# FSE_TSAL_trigger_schematic.net
KiCad netlist of a schematic drawn in EAGLE
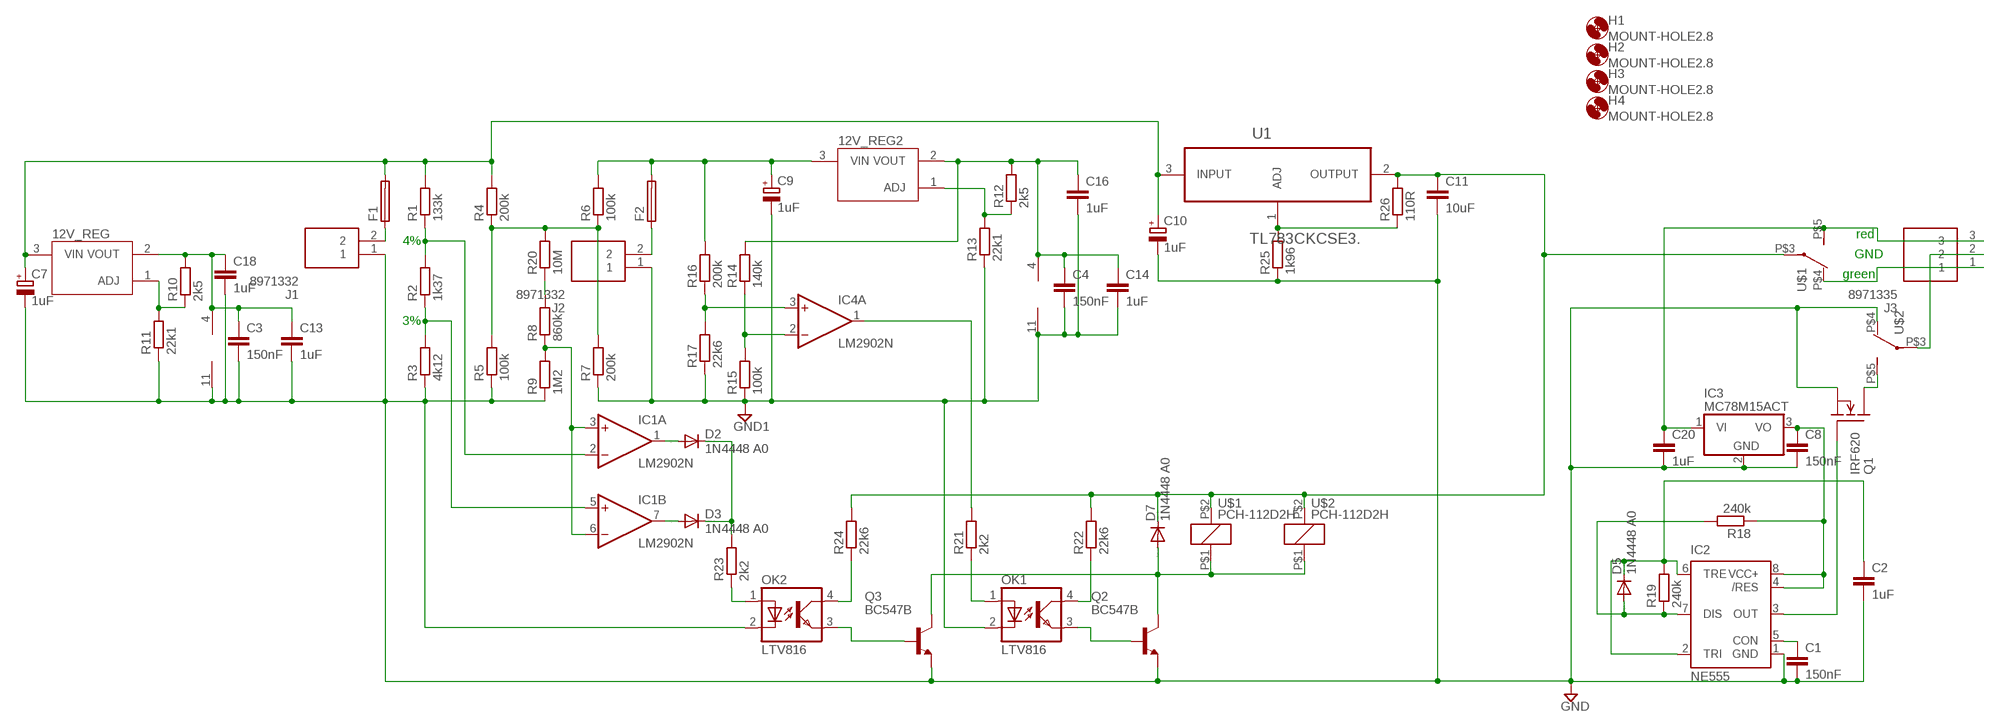
[diagram p0: schematic, sheet 1]

(export (version "E")
  (design (tool "Eeschema 10.0.6"))
  (components
    (comp (ref "12V_REG")
      (value "LR8LR8")
      (footprint "eagle-import:TO92-LINE")
      (libsource (lib "eagle-import") (part "LR8LR8"))
    )
    (comp (ref "12V_REG2")
      (value "LR8LR8")
      (footprint "eagle-import:TO92-LINE")
      (libsource (lib "eagle-import") (part "LR8LR8"))
    )
    (comp (ref "C1")
      (value "150nF")
      (footprint "eagle-import:C050-024X044")
      (libsource (lib "eagle-import") (part "C-EU050-024X044"))
    )
    (comp (ref "C2")
      (value "1uF")
      (footprint "eagle-import:C025-030X050")
      (libsource (lib "eagle-import") (part "C-EU025-030X050"))
    )
    (comp (ref "C3")
      (value "150nF")
      (footprint "eagle-import:C050-024X044")
      (libsource (lib "eagle-import") (part "C-EU050-024X044"))
    )
    (comp (ref "C4")
      (value "150nF")
      (footprint "eagle-import:C050-024X044")
      (libsource (lib "eagle-import") (part "C-EU050-024X044"))
    )
    (comp (ref "C7")
      (value "1uF")
      (footprint "eagle-import:E3,5-8")
      (libsource (lib "eagle-import") (part "CPOL-EUE3.5-8"))
    )
    (comp (ref "C8")
      (value "150nF")
      (footprint "eagle-import:C050-024X044")
      (libsource (lib "eagle-import") (part "C-EU050-024X044"))
    )
    (comp (ref "C9")
      (value "1uF")
      (footprint "eagle-import:E3,5-8")
      (libsource (lib "eagle-import") (part "CPOL-EUE3.5-8"))
    )
    (comp (ref "C10")
      (value "1uF")
      (footprint "eagle-import:E3,5-8")
      (libsource (lib "eagle-import") (part "CPOL-EUE3.5-8"))
    )
    (comp (ref "C11")
      (value "10uF")
      (footprint "eagle-import:C050-075X075")
      (libsource (lib "eagle-import") (part "C-EU050-075X075"))
    )
    (comp (ref "C13")
      (value "1uF")
      (footprint "eagle-import:C025-030X050")
      (libsource (lib "eagle-import") (part "C-EU025-030X050"))
    )
    (comp (ref "C14")
      (value "1uF")
      (footprint "eagle-import:C025-030X050")
      (libsource (lib "eagle-import") (part "C-EU025-030X050"))
    )
    (comp (ref "C16")
      (value "1uF")
      (footprint "eagle-import:C025-030X050")
      (libsource (lib "eagle-import") (part "C-EU025-030X050"))
    )
    (comp (ref "C18")
      (value "1uF")
      (footprint "eagle-import:C025-030X050")
      (libsource (lib "eagle-import") (part "C-EU025-030X050"))
    )
    (comp (ref "C20")
      (value "1uF")
      (footprint "eagle-import:C025-030X050")
      (libsource (lib "eagle-import") (part "C-EU025-030X050"))
    )
    (comp (ref "D2")
      (value "1N4448 A0")
      (footprint "eagle-import:DO35-10")
      (libsource (lib "eagle-import") (part "1N4446"))
    )
    (comp (ref "D3")
      (value "1N4448 A0")
      (footprint "eagle-import:DO35-10")
      (libsource (lib "eagle-import") (part "1N4446"))
    )
    (comp (ref "D5")
      (value "1N4448 A0")
      (footprint "eagle-import:DO35-10")
      (libsource (lib "eagle-import") (part "1N4446"))
    )
    (comp (ref "D7")
      (value "1N4448 A0")
      (footprint "eagle-import:DO35-10")
      (libsource (lib "eagle-import") (part "1N4446"))
    )
    (comp (ref "F1")
      (value "GSH15")
      (footprint "eagle-import:GSH15")
      (fields (field (name "MPN") "64900001039"))
      (libsource (lib "eagle-import") (part "GSH15"))
    )
    (comp (ref "F2")
      (value "GSH15")
      (footprint "eagle-import:GSH15")
      (fields (field (name "MPN") "64900001039"))
      (libsource (lib "eagle-import") (part "GSH15"))
    )
    (comp (ref "H1")
      (value "MOUNT-HOLE2.8")
      (footprint "eagle-import:2,8")
      (libsource (lib "eagle-import") (part "MOUNT-HOLE2.8"))
    )
    (comp (ref "H2")
      (value "MOUNT-HOLE2.8")
      (footprint "eagle-import:2,8")
      (libsource (lib "eagle-import") (part "MOUNT-HOLE2.8"))
    )
    (comp (ref "H3")
      (value "MOUNT-HOLE2.8")
      (footprint "eagle-import:2,8")
      (libsource (lib "eagle-import") (part "MOUNT-HOLE2.8"))
    )
    (comp (ref "H4")
      (value "MOUNT-HOLE2.8")
      (footprint "eagle-import:2,8")
      (libsource (lib "eagle-import") (part "MOUNT-HOLE2.8"))
    )
    (comp (ref "IC1")
      (value "LM2902N")
      (footprint "eagle-import:DIL14")
      (libsource (lib "eagle-import") (part "LM2902N"))
    )
    (comp (ref "IC2")
      (value "NE555")
      (footprint "eagle-import:DIL-08")
      (fields (field (name "MF") "Arrow Electronics") (field (name "MPN") "NE555N"))
      (libsource (lib "eagle-import") (part "NE555"))
    )
    (comp (ref "IC3")
      (value "MC78M15ACT")
      (footprint "eagle-import:TO220V")
      (libsource (lib "eagle-import") (part "MC78MT15AC"))
    )
    (comp (ref "IC4")
      (value "LM2902N")
      (footprint "eagle-import:DIL14")
      (libsource (lib "eagle-import") (part "LM2902N"))
    )
    (comp (ref "J1")
      (value "8971332")
      (footprint "eagle-import:SHDR2W90P0X350_1X2_700X700X850")
      (libsource (lib "eagle-import") (part "8971332"))
    )
    (comp (ref "J2")
      (value "8971332")
      (footprint "eagle-import:SHDR2W90P0X350_1X2_700X700X850")
      (libsource (lib "eagle-import") (part "8971332"))
    )
    (comp (ref "J3")
      (value "8971335")
      (footprint "eagle-import:SHDR3W90P0X350_1X3_1050X700X85")
      (libsource (lib "eagle-import") (part "8971335"))
    )
    (comp (ref "OK1")
      (value "LTV816")
      (footprint "eagle-import:DIL04")
      (libsource (lib "eagle-import") (part "LTV816"))
    )
    (comp (ref "OK2")
      (value "LTV816")
      (footprint "eagle-import:DIL04")
      (libsource (lib "eagle-import") (part "LTV816"))
    )
    (comp (ref "Q1")
      (value "IRF620")
      (footprint "eagle-import:TO220")
      (libsource (lib "eagle-import") (part "IRF620"))
    )
    (comp (ref "Q2")
      (value "BC547B")
      (footprint "eagle-import:TO92")
      (libsource (lib "eagle-import") (part "BC547B"))
    )
    (comp (ref "Q3")
      (value "BC547B")
      (footprint "eagle-import:TO92")
      (libsource (lib "eagle-import") (part "BC547B"))
    )
    (comp (ref "R1")
      (value "133k")
      (footprint "eagle-import:0207_10")
      (libsource (lib "eagle-import") (part "R-EU_0207/10"))
    )
    (comp (ref "R2")
      (value "1k37")
      (footprint "eagle-import:0207_10")
      (libsource (lib "eagle-import") (part "R-EU_0207/10"))
    )
    (comp (ref "R3")
      (value "4k12")
      (footprint "eagle-import:0207_10")
      (libsource (lib "eagle-import") (part "R-EU_0207/10"))
    )
    (comp (ref "R4")
      (value "200k")
      (footprint "eagle-import:0207_10")
      (libsource (lib "eagle-import") (part "R-EU_0207/10"))
    )
    (comp (ref "R5")
      (value "100k")
      (footprint "eagle-import:0207_10")
      (libsource (lib "eagle-import") (part "R-EU_0207/10"))
    )
    (comp (ref "R6")
      (value "100k")
      (footprint "eagle-import:0207_10")
      (libsource (lib "eagle-import") (part "R-EU_0207/10"))
    )
    (comp (ref "R7")
      (value "200k")
      (footprint "eagle-import:0207_10")
      (libsource (lib "eagle-import") (part "R-EU_0207/10"))
    )
    (comp (ref "R8")
      (value "860k")
      (footprint "eagle-import:0207_10")
      (libsource (lib "eagle-import") (part "R-EU_0207/10"))
    )
    (comp (ref "R9")
      (value "1M2")
      (footprint "eagle-import:0207_10")
      (libsource (lib "eagle-import") (part "R-EU_0207/10"))
    )
    (comp (ref "R10")
      (value "2k5")
      (footprint "eagle-import:0207_10")
      (libsource (lib "eagle-import") (part "R-EU_0207/10"))
    )
    (comp (ref "R11")
      (value "22k1")
      (footprint "eagle-import:0207_10")
      (libsource (lib "eagle-import") (part "R-EU_0207/10"))
    )
    (comp (ref "R12")
      (value "2k5")
      (footprint "eagle-import:0207_10")
      (libsource (lib "eagle-import") (part "R-EU_0207/10"))
    )
    (comp (ref "R13")
      (value "22k1")
      (footprint "eagle-import:0207_10")
      (libsource (lib "eagle-import") (part "R-EU_0207/10"))
    )
    (comp (ref "R14")
      (value "140k")
      (footprint "eagle-import:0207_10")
      (libsource (lib "eagle-import") (part "R-EU_0207/10"))
    )
    (comp (ref "R15")
      (value "100k")
      (footprint "eagle-import:0207_10")
      (libsource (lib "eagle-import") (part "R-EU_0207/10"))
    )
    (comp (ref "R16")
      (value "200k")
      (footprint "eagle-import:0207_10")
      (libsource (lib "eagle-import") (part "R-EU_0207/10"))
    )
    (comp (ref "R17")
      (value "22k6")
      (footprint "eagle-import:0207_10")
      (libsource (lib "eagle-import") (part "R-EU_0207/10"))
    )
    (comp (ref "R18")
      (value "240k")
      (footprint "eagle-import:0207_10")
      (libsource (lib "eagle-import") (part "R-EU_0207/10"))
    )
    (comp (ref "R19")
      (value "240k")
      (footprint "eagle-import:0207_10")
      (libsource (lib "eagle-import") (part "R-EU_0207/10"))
    )
    (comp (ref "R20")
      (value "10M")
      (footprint "eagle-import:0207_10")
      (libsource (lib "eagle-import") (part "R-EU_0207/10"))
    )
    (comp (ref "R21")
      (value "2k2")
      (footprint "eagle-import:0207_10")
      (libsource (lib "eagle-import") (part "R-EU_0207/10"))
    )
    (comp (ref "R22")
      (value "22k6")
      (footprint "eagle-import:0207_10")
      (libsource (lib "eagle-import") (part "R-EU_0207/10"))
    )
    (comp (ref "R23")
      (value "2k2")
      (footprint "eagle-import:0207_10")
      (libsource (lib "eagle-import") (part "R-EU_0207/10"))
    )
    (comp (ref "R24")
      (value "22k6")
      (footprint "eagle-import:0207_10")
      (libsource (lib "eagle-import") (part "R-EU_0207/10"))
    )
    (comp (ref "R25")
      (value "1k96")
      (footprint "eagle-import:0309_10")
      (libsource (lib "eagle-import") (part "R-EU_0309/10"))
    )
    (comp (ref "R26")
      (value "110R")
      (footprint "eagle-import:0309_10")
      (libsource (lib "eagle-import") (part "R-EU_0309/10"))
    )
    (comp (ref "U$1")
      (value "PCH-112D2H")
      (footprint "eagle-import:PCH-112D2H")
      (libsource (lib "eagle-import") (part "PCH-112D2H"))
    )
    (comp (ref "U$2")
      (value "PCH-112D2H")
      (footprint "eagle-import:PCH-112D2H")
      (libsource (lib "eagle-import") (part "PCH-112D2H"))
    )
    (comp (ref "U1")
      (value "TL783CKCSE3.")
      (footprint "eagle-import:TO254P457X1016X2222-3P")
      (libsource (lib "eagle-import") (part "TL783CKCSE3."))
    )
  )
  (nets
    (net (code "1") (name "GND") (class "Default")
      (node (ref "C1") (pin "2") (pinfunction "2_2") (pintype "passive"))
      (node (ref "C10") (pin "-") (pinfunction "-_-") (pintype "passive"))
      (node (ref "C11") (pin "2") (pinfunction "2_2") (pintype "passive"))
      (node (ref "C13") (pin "2") (pinfunction "2_2") (pintype "passive"))
      (node (ref "C18") (pin "2") (pinfunction "2_2") (pintype "passive"))
      (node (ref "C2") (pin "2") (pinfunction "2_2") (pintype "passive"))
      (node (ref "C20") (pin "2") (pinfunction "2_2") (pintype "passive"))
      (node (ref "C3") (pin "2") (pinfunction "2_2") (pintype "passive"))
      (node (ref "C7") (pin "-") (pinfunction "-_-") (pintype "passive"))
      (node (ref "C8") (pin "2") (pinfunction "2_2") (pintype "passive"))
      (node (ref "IC1") (pin "11") (pinfunction "V-_11") (pintype "power_in"))
      (node (ref "IC2") (pin "1") (pinfunction "GND_1") (pintype "power_in"))
      (node (ref "IC3") (pin "2") (pinfunction "GND_2") (pintype "passive"))
      (node (ref "J1") (pin "1") (pinfunction "1_1") (pintype "bidirectional"))
      (node (ref "OK2") (pin "2") (pinfunction "C_2") (pintype "passive"))
      (node (ref "Q1") (pin "3") (pinfunction "S_3") (pintype "passive"))
      (node (ref "Q2") (pin "1") (pinfunction "E_1") (pintype "passive"))
      (node (ref "Q3") (pin "1") (pinfunction "E_1") (pintype "passive"))
      (node (ref "R11") (pin "1") (pinfunction "1_1") (pintype "passive"))
      (node (ref "R25") (pin "1") (pinfunction "1_1") (pintype "passive"))
      (node (ref "R3") (pin "1") (pinfunction "1_1") (pintype "passive"))
      (node (ref "R5") (pin "1") (pinfunction "1_1") (pintype "passive"))
      (node (ref "R9") (pin "1") (pinfunction "1_1") (pintype "passive"))
      (node (ref "U$2") (pin "P$4") (pinfunction "O_P$4") (pintype "passive"))
    )
    (net (code "2") (name "GND1") (class "Default")
      (node (ref "C14") (pin "2") (pinfunction "2_2") (pintype "passive"))
      (node (ref "C16") (pin "2") (pinfunction "2_2") (pintype "passive"))
      (node (ref "C4") (pin "2") (pinfunction "2_2") (pintype "passive"))
      (node (ref "C9") (pin "-") (pinfunction "-_-") (pintype "passive"))
      (node (ref "IC4") (pin "11") (pinfunction "V-_11") (pintype "power_in"))
      (node (ref "J2") (pin "1") (pinfunction "1_1") (pintype "bidirectional"))
      (node (ref "OK1") (pin "2") (pinfunction "C_2") (pintype "passive"))
      (node (ref "R13") (pin "1") (pinfunction "1_1") (pintype "passive"))
      (node (ref "R15") (pin "1") (pinfunction "1_1") (pintype "passive"))
      (node (ref "R17") (pin "1") (pinfunction "1_1") (pintype "passive"))
      (node (ref "R7") (pin "1") (pinfunction "1_1") (pintype "passive"))
    )
    (net (code "3") (name "Net-(12V_REG-ADJ)") (class "Default")
      (node (ref "12V_REG") (pin "1") (pinfunction "ADJ_1") (pintype "bidirectional"))
      (node (ref "R10") (pin "1") (pinfunction "1_1") (pintype "passive"))
      (node (ref "R11") (pin "2") (pinfunction "2_2") (pintype "passive"))
    )
    (net (code "4") (name "Net-(12V_REG-VIN)") (class "Default")
      (node (ref "12V_REG") (pin "3") (pinfunction "VIN_3") (pintype "bidirectional"))
      (node (ref "C10") (pin "+") (pinfunction "+_+") (pintype "passive"))
      (node (ref "C7") (pin "+") (pinfunction "+_+") (pintype "passive"))
      (node (ref "F1") (pin "2") (pinfunction "2_2") (pintype "passive"))
      (node (ref "R1") (pin "2") (pinfunction "2_2") (pintype "passive"))
      (node (ref "R4") (pin "2") (pinfunction "2_2") (pintype "passive"))
      (node (ref "U1") (pin "3") (pinfunction "INPUT_3") (pintype "input"))
    )
    (net (code "5") (name "Net-(12V_REG-VOUT)") (class "Default")
      (node (ref "12V_REG") (pin "2") (pinfunction "VOUT_2") (pintype "bidirectional"))
      (node (ref "C13") (pin "1") (pinfunction "1_1") (pintype "passive"))
      (node (ref "C18") (pin "1") (pinfunction "1_1") (pintype "passive"))
      (node (ref "C3") (pin "1") (pinfunction "1_1") (pintype "passive"))
      (node (ref "IC1") (pin "4") (pinfunction "V+_4") (pintype "power_in"))
      (node (ref "R10") (pin "2") (pinfunction "2_2") (pintype "passive"))
    )
    (net (code "6") (name "Net-(12V_REG2-ADJ)") (class "Default")
      (node (ref "12V_REG2") (pin "1") (pinfunction "ADJ_1") (pintype "bidirectional"))
      (node (ref "R12") (pin "1") (pinfunction "1_1") (pintype "passive"))
      (node (ref "R13") (pin "2") (pinfunction "2_2") (pintype "passive"))
    )
    (net (code "7") (name "Net-(12V_REG2-VIN)") (class "Default")
      (node (ref "12V_REG2") (pin "3") (pinfunction "VIN_3") (pintype "bidirectional"))
      (node (ref "C9") (pin "+") (pinfunction "+_+") (pintype "passive"))
      (node (ref "F2") (pin "2") (pinfunction "2_2") (pintype "passive"))
      (node (ref "R16") (pin "2") (pinfunction "2_2") (pintype "passive"))
      (node (ref "R6") (pin "2") (pinfunction "2_2") (pintype "passive"))
    )
    (net (code "8") (name "Net-(12V_REG2-VOUT)") (class "Default")
      (node (ref "12V_REG2") (pin "2") (pinfunction "VOUT_2") (pintype "bidirectional"))
      (node (ref "C14") (pin "1") (pinfunction "1_1") (pintype "passive"))
      (node (ref "C16") (pin "1") (pinfunction "1_1") (pintype "passive"))
      (node (ref "C4") (pin "1") (pinfunction "1_1") (pintype "passive"))
      (node (ref "IC4") (pin "4") (pinfunction "V+_4") (pintype "power_in"))
      (node (ref "R12") (pin "2") (pinfunction "2_2") (pintype "passive"))
      (node (ref "R14") (pin "2") (pinfunction "2_2") (pintype "passive"))
    )
    (net (code "9") (name "Net-(D2-PadC)") (class "Default")
      (node (ref "D2") (pin "C") (pinfunction "C_C") (pintype "passive"))
      (node (ref "D3") (pin "C") (pinfunction "C_C") (pintype "passive"))
      (node (ref "R23") (pin "2") (pinfunction "2_2") (pintype "passive"))
    )
    (net (code "10") (name "Net-(F1-Pad1)") (class "Default")
      (node (ref "F1") (pin "1") (pinfunction "1_1") (pintype "passive"))
      (node (ref "J1") (pin "2") (pinfunction "2_2") (pintype "bidirectional"))
    )
    (net (code "11") (name "Net-(F2-Pad1)") (class "Default")
      (node (ref "F2") (pin "1") (pinfunction "1_1") (pintype "passive"))
      (node (ref "J2") (pin "2") (pinfunction "2_2") (pintype "bidirectional"))
    )
    (net (code "12") (name "Net-(IC1A-+IN)") (class "Default")
      (node (ref "IC1") (pin "3") (pinfunction "+IN_3") (pintype "input"))
      (node (ref "IC1") (pin "6") (pinfunction "-IN_6") (pintype "input"))
      (node (ref "R8") (pin "1") (pinfunction "1_1") (pintype "passive"))
      (node (ref "R9") (pin "2") (pinfunction "2_2") (pintype "passive"))
    )
    (net (code "13") (name "Net-(IC1A--IN)") (class "Default")
      (node (ref "IC1") (pin "2") (pinfunction "-IN_2") (pintype "input"))
      (node (ref "R1") (pin "1") (pinfunction "1_1") (pintype "passive"))
      (node (ref "R2") (pin "2") (pinfunction "2_2") (pintype "passive"))
    )
    (net (code "14") (name "Net-(IC1A-OUT)") (class "Default")
      (node (ref "D2") (pin "A") (pinfunction "A_A") (pintype "passive"))
      (node (ref "IC1") (pin "1") (pinfunction "OUT_1") (pintype "output"))
    )
    (net (code "15") (name "Net-(IC1B-+IN)") (class "Default")
      (node (ref "IC1") (pin "5") (pinfunction "+IN_5") (pintype "input"))
      (node (ref "R2") (pin "1") (pinfunction "1_1") (pintype "passive"))
      (node (ref "R3") (pin "2") (pinfunction "2_2") (pintype "passive"))
    )
    (net (code "16") (name "Net-(IC1B-OUT)") (class "Default")
      (node (ref "D3") (pin "A") (pinfunction "A_A") (pintype "passive"))
      (node (ref "IC1") (pin "7") (pinfunction "OUT_7") (pintype "output"))
    )
    (net (code "17") (name "Net-(IC2-CON)") (class "Default")
      (node (ref "C1") (pin "1") (pinfunction "1_1") (pintype "passive"))
      (node (ref "IC2") (pin "5") (pinfunction "CON_5") (pintype "input"))
    )
    (net (code "18") (name "Net-(IC2-DIS)") (class "Default")
      (node (ref "D5") (pin "A") (pinfunction "A_A") (pintype "passive"))
      (node (ref "IC2") (pin "7") (pinfunction "DIS_7") (pintype "input"))
      (node (ref "R18") (pin "2") (pinfunction "2_2") (pintype "passive"))
      (node (ref "R19") (pin "1") (pinfunction "1_1") (pintype "passive"))
    )
    (net (code "19") (name "Net-(IC2-OUT)") (class "Default")
      (node (ref "IC2") (pin "3") (pinfunction "OUT_3") (pintype "output"))
      (node (ref "Q1") (pin "1") (pinfunction "G_1") (pintype "passive"))
    )
    (net (code "20") (name "Net-(IC2-TRE)") (class "Default")
      (node (ref "C2") (pin "1") (pinfunction "1_1") (pintype "passive"))
      (node (ref "D5") (pin "C") (pinfunction "C_C") (pintype "passive"))
      (node (ref "IC2") (pin "2") (pinfunction "TRI_2") (pintype "input"))
      (node (ref "IC2") (pin "6") (pinfunction "TRE_6") (pintype "input"))
      (node (ref "R19") (pin "2") (pinfunction "2_2") (pintype "passive"))
    )
    (net (code "21") (name "Net-(IC2-VCC+)") (class "Default")
      (node (ref "C8") (pin "1") (pinfunction "1_1") (pintype "passive"))
      (node (ref "IC2") (pin "4") (pinfunction "/RES_4") (pintype "input"))
      (node (ref "IC2") (pin "8") (pinfunction "VCC+_8") (pintype "power_in"))
      (node (ref "IC3") (pin "3") (pinfunction "VO_3") (pintype "passive"))
      (node (ref "R18") (pin "1") (pinfunction "1_1") (pintype "passive"))
    )
    (net (code "22") (name "Net-(IC3-VI)") (class "Default")
      (node (ref "C20") (pin "1") (pinfunction "1_1") (pintype "passive"))
      (node (ref "IC3") (pin "1") (pinfunction "VI_1") (pintype "input"))
      (node (ref "J3") (pin "3") (pinfunction "3_3") (pintype "bidirectional"))
      (node (ref "U$1") (pin "P$5") (pinfunction "S_P$5") (pintype "passive"))
    )
    (net (code "23") (name "Net-(IC4A-+IN)") (class "Default")
      (node (ref "IC4") (pin "3") (pinfunction "+IN_3") (pintype "input"))
      (node (ref "R16") (pin "1") (pinfunction "1_1") (pintype "passive"))
      (node (ref "R17") (pin "2") (pinfunction "2_2") (pintype "passive"))
    )
    (net (code "24") (name "Net-(IC4A--IN)") (class "Default")
      (node (ref "IC4") (pin "2") (pinfunction "-IN_2") (pintype "input"))
      (node (ref "R14") (pin "1") (pinfunction "1_1") (pintype "passive"))
      (node (ref "R15") (pin "2") (pinfunction "2_2") (pintype "passive"))
    )
    (net (code "25") (name "Net-(IC4A-OUT)") (class "Default")
      (node (ref "IC4") (pin "1") (pinfunction "OUT_1") (pintype "output"))
      (node (ref "R21") (pin "2") (pinfunction "2_2") (pintype "passive"))
    )
    (net (code "26") (name "Net-(OK1-A)") (class "Default")
      (node (ref "OK1") (pin "1") (pinfunction "A_1") (pintype "passive"))
      (node (ref "R21") (pin "1") (pinfunction "1_1") (pintype "passive"))
    )
    (net (code "27") (name "Net-(OK1-COL)") (class "Default")
      (node (ref "OK1") (pin "4") (pinfunction "COL_4") (pintype "passive"))
      (node (ref "R22") (pin "1") (pinfunction "1_1") (pintype "passive"))
    )
    (net (code "28") (name "Net-(OK1-EMIT)") (class "Default")
      (node (ref "OK1") (pin "3") (pinfunction "EMIT_3") (pintype "passive"))
      (node (ref "Q2") (pin "2") (pinfunction "B_2") (pintype "passive"))
    )
    (net (code "29") (name "Net-(OK2-A)") (class "Default")
      (node (ref "OK2") (pin "1") (pinfunction "A_1") (pintype "passive"))
      (node (ref "R23") (pin "1") (pinfunction "1_1") (pintype "passive"))
    )
    (net (code "30") (name "Net-(OK2-COL)") (class "Default")
      (node (ref "OK2") (pin "4") (pinfunction "COL_4") (pintype "passive"))
      (node (ref "R24") (pin "1") (pinfunction "1_1") (pintype "passive"))
    )
    (net (code "31") (name "Net-(OK2-EMIT)") (class "Default")
      (node (ref "OK2") (pin "3") (pinfunction "EMIT_3") (pintype "passive"))
      (node (ref "Q3") (pin "2") (pinfunction "B_2") (pintype "passive"))
    )
    (net (code "32") (name "Net-(Q1-D)") (class "Default")
      (node (ref "Q1") (pin "2") (pinfunction "D_2") (pintype "passive"))
      (node (ref "U$2") (pin "P$5") (pinfunction "S_P$5") (pintype "passive"))
    )
    (net (code "33") (name "Net-(Q2-C)") (class "Default")
      (node (ref "D7") (pin "A") (pinfunction "A_A") (pintype "passive"))
      (node (ref "Q2") (pin "3") (pinfunction "C_3") (pintype "passive"))
      (node (ref "Q3") (pin "3") (pinfunction "C_3") (pintype "passive"))
      (node (ref "U$1") (pin "P$1") (pinfunction "2_P$1") (pintype "passive"))
      (node (ref "U$2") (pin "P$1") (pinfunction "2_P$1") (pintype "passive"))
    )
    (net (code "34") (name "Net-(R20-Pad1)") (class "Default")
      (node (ref "R20") (pin "1") (pinfunction "1_1") (pintype "passive"))
      (node (ref "R8") (pin "2") (pinfunction "2_2") (pintype "passive"))
    )
    (net (code "35") (name "Net-(R20-Pad2)") (class "Default")
      (node (ref "R20") (pin "2") (pinfunction "2_2") (pintype "passive"))
      (node (ref "R4") (pin "1") (pinfunction "1_1") (pintype "passive"))
      (node (ref "R5") (pin "2") (pinfunction "2_2") (pintype "passive"))
      (node (ref "R6") (pin "1") (pinfunction "1_1") (pintype "passive"))
      (node (ref "R7") (pin "2") (pinfunction "2_2") (pintype "passive"))
    )
    (net (code "36") (name "Net-(U$1A-1)") (class "Default")
      (node (ref "C11") (pin "1") (pinfunction "1_1") (pintype "passive"))
      (node (ref "D7") (pin "C") (pinfunction "C_C") (pintype "passive"))
      (node (ref "R22") (pin "2") (pinfunction "2_2") (pintype "passive"))
      (node (ref "R24") (pin "2") (pinfunction "2_2") (pintype "passive"))
      (node (ref "R26") (pin "2") (pinfunction "2_2") (pintype "passive"))
      (node (ref "U$1") (pin "P$2") (pinfunction "1_P$2") (pintype "passive"))
      (node (ref "U$1") (pin "P$3") (pinfunction "P_P$3") (pintype "passive"))
      (node (ref "U$2") (pin "P$2") (pinfunction "1_P$2") (pintype "passive"))
      (node (ref "U1") (pin "2") (pinfunction "OUTPUT_2") (pintype "output"))
    )
    (net (code "37") (name "Net-(U$1B-O)") (class "Default")
      (node (ref "J3") (pin "1") (pinfunction "1_1") (pintype "bidirectional"))
      (node (ref "U$1") (pin "P$4") (pinfunction "O_P$4") (pintype "passive"))
    )
    (net (code "38") (name "Net-(U$2B-P)") (class "Default")
      (node (ref "J3") (pin "2") (pinfunction "2_2") (pintype "bidirectional"))
      (node (ref "U$2") (pin "P$3") (pinfunction "P_P$3") (pintype "passive"))
    )
    (net (code "39") (name "Net-(U1-ADJ)") (class "Default")
      (node (ref "R25") (pin "2") (pinfunction "2_2") (pintype "passive"))
      (node (ref "R26") (pin "1") (pinfunction "1_1") (pintype "passive"))
      (node (ref "U1") (pin "1") (pinfunction "ADJ_1") (pintype "passive"))
    )
  )
)
